# MSSRP-Microcontroller.net
KiCad netlist of a schematic drawn in EAGLE
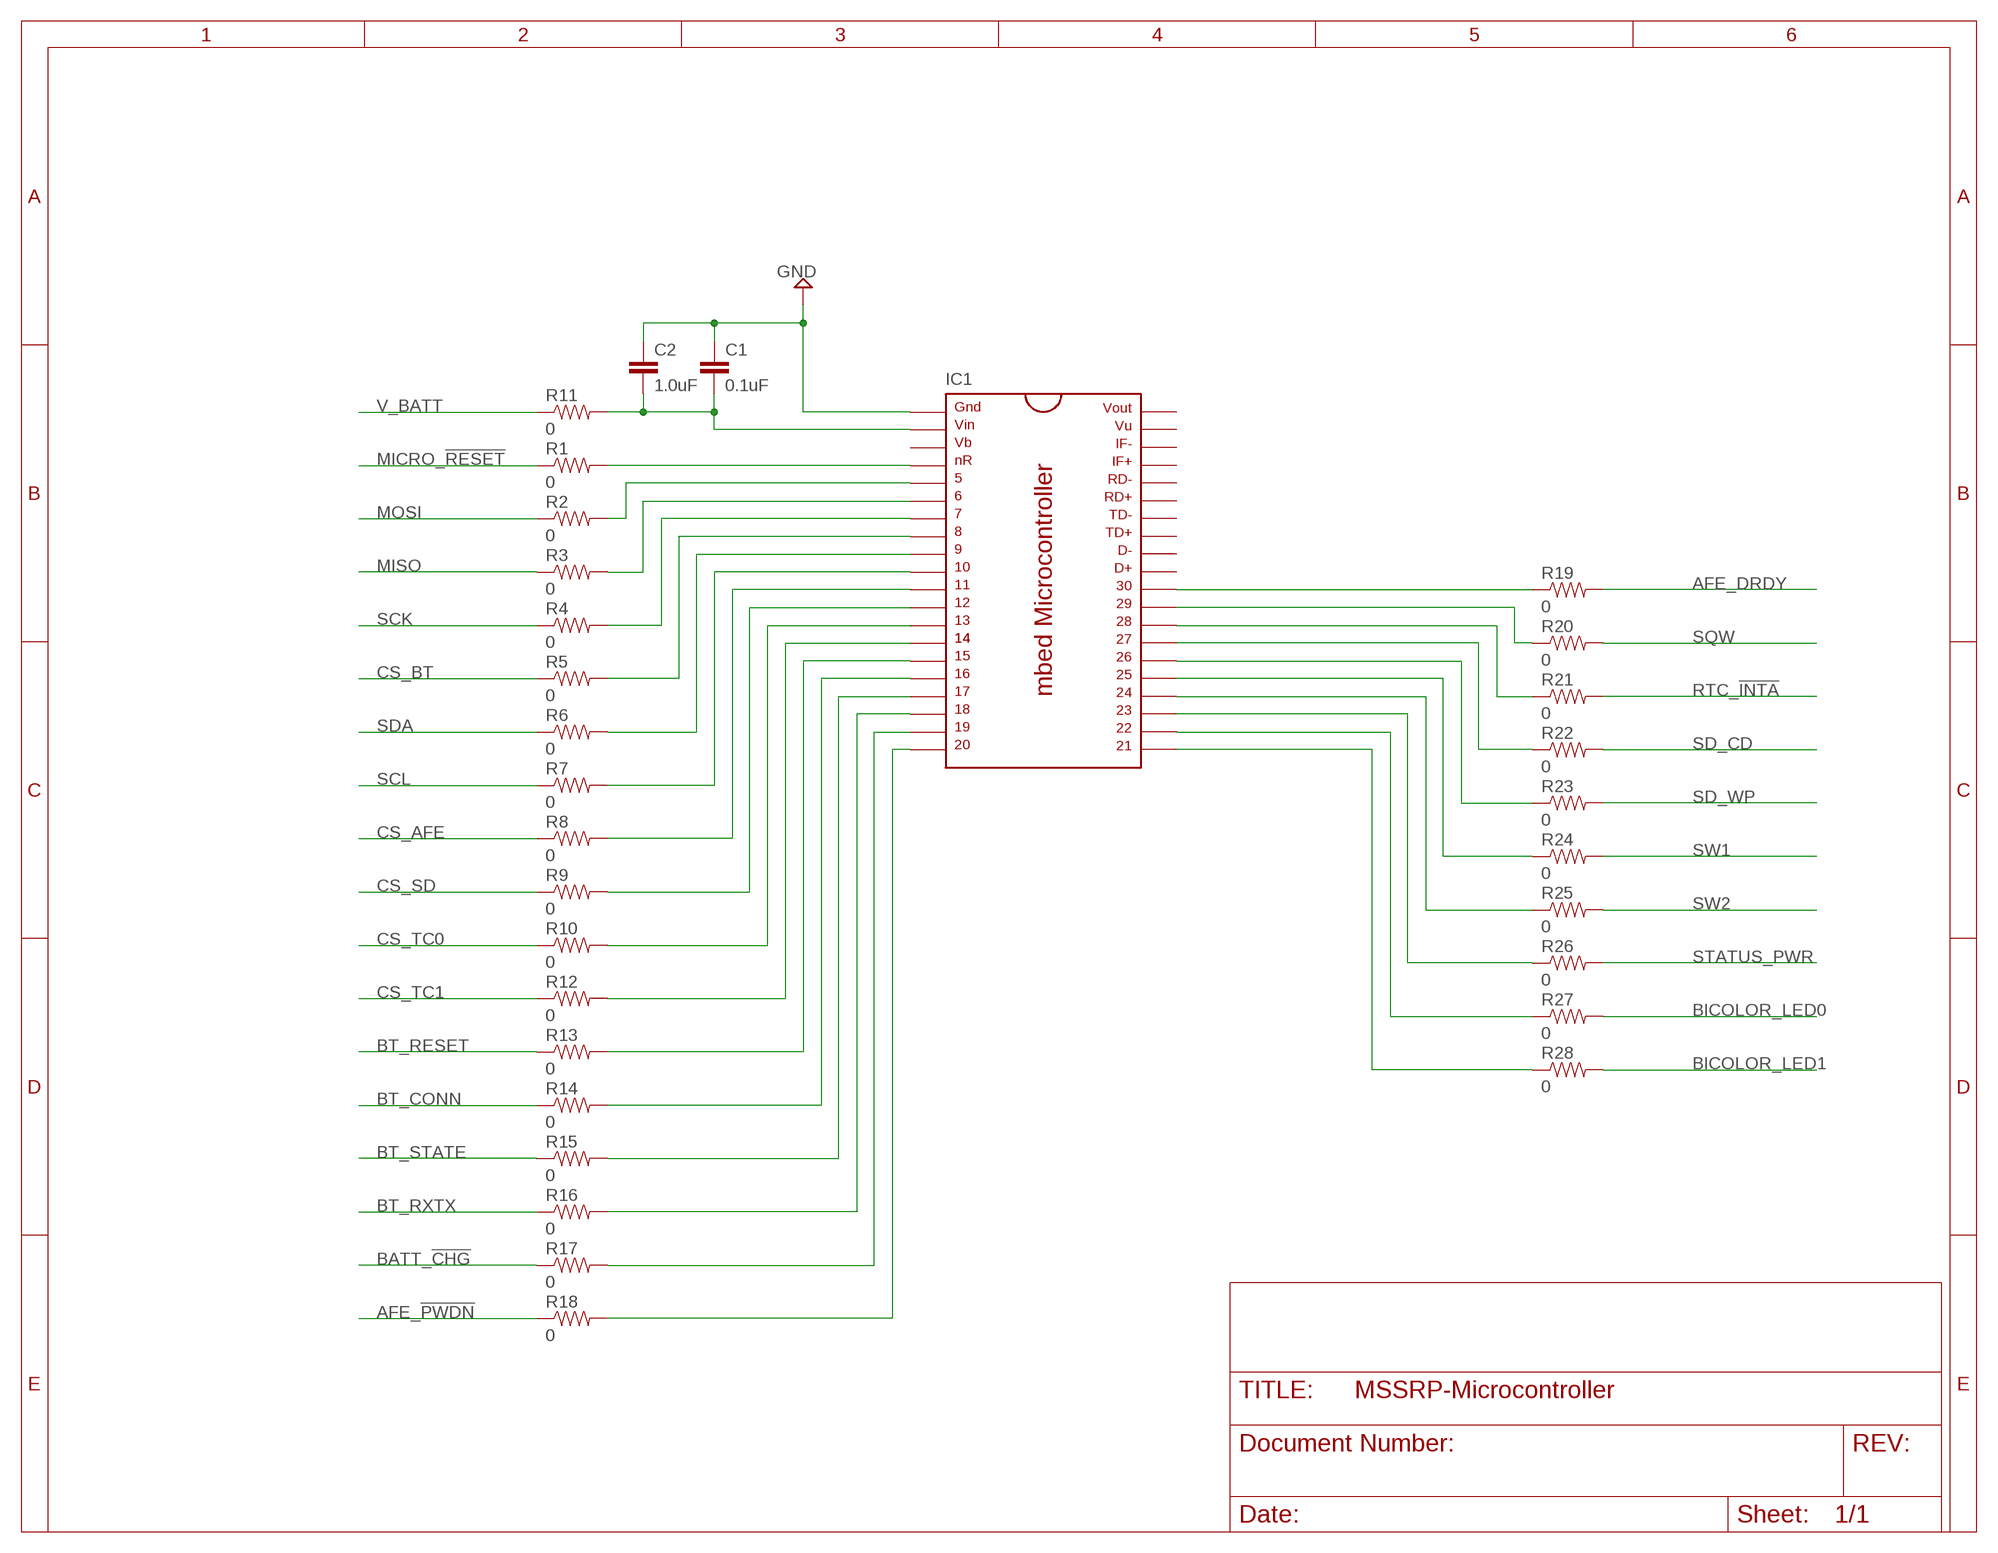
[diagram p0: schematic, sheet 1]

(export (version "E")
  (design (tool "Eeschema 10.0.6"))
  (components
    (comp (ref "C1")
      (value "0.1uF")
      (footprint "eagle-import:0603-CAP")
      (libsource (lib "eagle-import") (part "0.1UF-25V-5%(0603)"))
    )
    (comp (ref "C2")
      (value "1.0uF")
      (footprint "eagle-import:0603-CAP")
      (libsource (lib "eagle-import") (part "1.0UF-16V-10%(0603)"))
    )
    (comp (ref "IC1")
      (value "MBED")
      (footprint "eagle-import:DIL40_0.9")
      (libsource (lib "eagle-import") (part "MBED"))
    )
    (comp (ref "R1")
      (value "0")
      (footprint "eagle-import:0603")
      (libsource (lib "eagle-import") (part "0OHM1/10W5%(0603)"))
    )
    (comp (ref "R2")
      (value "0")
      (footprint "eagle-import:0603")
      (libsource (lib "eagle-import") (part "0OHM1/10W5%(0603)"))
    )
    (comp (ref "R3")
      (value "0")
      (footprint "eagle-import:0603")
      (libsource (lib "eagle-import") (part "0OHM1/10W5%(0603)"))
    )
    (comp (ref "R4")
      (value "0")
      (footprint "eagle-import:0603")
      (libsource (lib "eagle-import") (part "0OHM1/10W5%(0603)"))
    )
    (comp (ref "R5")
      (value "0")
      (footprint "eagle-import:0603")
      (libsource (lib "eagle-import") (part "0OHM1/10W5%(0603)"))
    )
    (comp (ref "R6")
      (value "0")
      (footprint "eagle-import:0603")
      (libsource (lib "eagle-import") (part "0OHM1/10W5%(0603)"))
    )
    (comp (ref "R7")
      (value "0")
      (footprint "eagle-import:0603")
      (libsource (lib "eagle-import") (part "0OHM1/10W5%(0603)"))
    )
    (comp (ref "R8")
      (value "0")
      (footprint "eagle-import:0603")
      (libsource (lib "eagle-import") (part "0OHM1/10W5%(0603)"))
    )
    (comp (ref "R9")
      (value "0")
      (footprint "eagle-import:0603")
      (libsource (lib "eagle-import") (part "0OHM1/10W5%(0603)"))
    )
    (comp (ref "R10")
      (value "0")
      (footprint "eagle-import:0603")
      (libsource (lib "eagle-import") (part "0OHM1/10W5%(0603)"))
    )
    (comp (ref "R11")
      (value "0")
      (footprint "eagle-import:0603")
      (libsource (lib "eagle-import") (part "0OHM1/10W5%(0603)"))
    )
    (comp (ref "R12")
      (value "0")
      (footprint "eagle-import:0603")
      (libsource (lib "eagle-import") (part "0OHM1/10W5%(0603)"))
    )
    (comp (ref "R13")
      (value "0")
      (footprint "eagle-import:0603")
      (libsource (lib "eagle-import") (part "0OHM1/10W5%(0603)"))
    )
    (comp (ref "R14")
      (value "0")
      (footprint "eagle-import:0603")
      (libsource (lib "eagle-import") (part "0OHM1/10W5%(0603)"))
    )
    (comp (ref "R15")
      (value "0")
      (footprint "eagle-import:0603")
      (libsource (lib "eagle-import") (part "0OHM1/10W5%(0603)"))
    )
    (comp (ref "R16")
      (value "0")
      (footprint "eagle-import:0603")
      (libsource (lib "eagle-import") (part "0OHM1/10W5%(0603)"))
    )
    (comp (ref "R17")
      (value "0")
      (footprint "eagle-import:0603")
      (libsource (lib "eagle-import") (part "0OHM1/10W5%(0603)"))
    )
    (comp (ref "R18")
      (value "0")
      (footprint "eagle-import:0603")
      (libsource (lib "eagle-import") (part "0OHM1/10W5%(0603)"))
    )
    (comp (ref "R19")
      (value "0")
      (footprint "eagle-import:0603")
      (libsource (lib "eagle-import") (part "0OHM1/10W5%(0603)"))
    )
    (comp (ref "R20")
      (value "0")
      (footprint "eagle-import:0603")
      (libsource (lib "eagle-import") (part "0OHM1/10W5%(0603)"))
    )
    (comp (ref "R21")
      (value "0")
      (footprint "eagle-import:0603")
      (libsource (lib "eagle-import") (part "0OHM1/10W5%(0603)"))
    )
    (comp (ref "R22")
      (value "0")
      (footprint "eagle-import:0603")
      (libsource (lib "eagle-import") (part "0OHM1/10W5%(0603)"))
    )
    (comp (ref "R23")
      (value "0")
      (footprint "eagle-import:0603")
      (libsource (lib "eagle-import") (part "0OHM1/10W5%(0603)"))
    )
    (comp (ref "R24")
      (value "0")
      (footprint "eagle-import:0603")
      (libsource (lib "eagle-import") (part "0OHM1/10W5%(0603)"))
    )
    (comp (ref "R25")
      (value "0")
      (footprint "eagle-import:0603")
      (libsource (lib "eagle-import") (part "0OHM1/10W5%(0603)"))
    )
    (comp (ref "R26")
      (value "0")
      (footprint "eagle-import:0603")
      (libsource (lib "eagle-import") (part "0OHM1/10W5%(0603)"))
    )
    (comp (ref "R27")
      (value "0")
      (footprint "eagle-import:0603")
      (libsource (lib "eagle-import") (part "0OHM1/10W5%(0603)"))
    )
    (comp (ref "R28")
      (value "0")
      (footprint "eagle-import:0603")
      (libsource (lib "eagle-import") (part "0OHM1/10W5%(0603)"))
    )
  )
  (nets
    (net (code "1") (name "/AFE_DRDY") (class "Default")
      (node (ref "R19") (pin "2") (pinfunction "2_2") (pintype "passive"))
    )
    (net (code "2") (name "/AFE_~{PWDN}") (class "Default")
      (node (ref "R18") (pin "1") (pinfunction "1_1") (pintype "passive"))
    )
    (net (code "3") (name "/BATT_~{CHG}") (class "Default")
      (node (ref "R17") (pin "1") (pinfunction "1_1") (pintype "passive"))
    )
    (net (code "4") (name "/BICOLOR_LED0") (class "Default")
      (node (ref "R27") (pin "2") (pinfunction "2_2") (pintype "passive"))
    )
    (net (code "5") (name "/BICOLOR_LED1") (class "Default")
      (node (ref "R28") (pin "2") (pinfunction "2_2") (pintype "passive"))
    )
    (net (code "6") (name "/BT_CONN") (class "Default")
      (node (ref "R14") (pin "1") (pinfunction "1_1") (pintype "passive"))
    )
    (net (code "7") (name "/BT_RESET") (class "Default")
      (node (ref "R13") (pin "1") (pinfunction "1_1") (pintype "passive"))
    )
    (net (code "8") (name "/BT_RXTX") (class "Default")
      (node (ref "R16") (pin "1") (pinfunction "1_1") (pintype "passive"))
    )
    (net (code "9") (name "/BT_STATE") (class "Default")
      (node (ref "R15") (pin "1") (pinfunction "1_1") (pintype "passive"))
    )
    (net (code "10") (name "/CS_AFE") (class "Default")
      (node (ref "R8") (pin "1") (pinfunction "1_1") (pintype "passive"))
    )
    (net (code "11") (name "/CS_BT") (class "Default")
      (node (ref "R5") (pin "1") (pinfunction "1_1") (pintype "passive"))
    )
    (net (code "12") (name "/CS_SD") (class "Default")
      (node (ref "R9") (pin "1") (pinfunction "1_1") (pintype "passive"))
    )
    (net (code "13") (name "/CS_TC0") (class "Default")
      (node (ref "R10") (pin "1") (pinfunction "1_1") (pintype "passive"))
    )
    (net (code "14") (name "/CS_TC1") (class "Default")
      (node (ref "R12") (pin "1") (pinfunction "1_1") (pintype "passive"))
    )
    (net (code "15") (name "/MICRO_~{RESET}") (class "Default")
      (node (ref "R1") (pin "1") (pinfunction "1_1") (pintype "passive"))
    )
    (net (code "16") (name "/MISO") (class "Default")
      (node (ref "R3") (pin "1") (pinfunction "1_1") (pintype "passive"))
    )
    (net (code "17") (name "/MOSI") (class "Default")
      (node (ref "R2") (pin "1") (pinfunction "1_1") (pintype "passive"))
    )
    (net (code "18") (name "/RTC_~{INTA}") (class "Default")
      (node (ref "R21") (pin "2") (pinfunction "2_2") (pintype "passive"))
    )
    (net (code "19") (name "/SCK") (class "Default")
      (node (ref "R4") (pin "1") (pinfunction "1_1") (pintype "passive"))
    )
    (net (code "20") (name "/SCL") (class "Default")
      (node (ref "R7") (pin "1") (pinfunction "1_1") (pintype "passive"))
    )
    (net (code "21") (name "/SDA") (class "Default")
      (node (ref "R6") (pin "1") (pinfunction "1_1") (pintype "passive"))
    )
    (net (code "22") (name "/SD_CD") (class "Default")
      (node (ref "R22") (pin "2") (pinfunction "2_2") (pintype "passive"))
    )
    (net (code "23") (name "/SD_WP") (class "Default")
      (node (ref "R23") (pin "2") (pinfunction "2_2") (pintype "passive"))
    )
    (net (code "24") (name "/SQW") (class "Default")
      (node (ref "R20") (pin "2") (pinfunction "2_2") (pintype "passive"))
    )
    (net (code "25") (name "/STATUS_PWR") (class "Default")
      (node (ref "R26") (pin "2") (pinfunction "2_2") (pintype "passive"))
    )
    (net (code "26") (name "/SW1") (class "Default")
      (node (ref "R24") (pin "2") (pinfunction "2_2") (pintype "passive"))
    )
    (net (code "27") (name "/SW2") (class "Default")
      (node (ref "R25") (pin "2") (pinfunction "2_2") (pintype "passive"))
    )
    (net (code "28") (name "/V_BATT") (class "Default")
      (node (ref "R11") (pin "1") (pinfunction "1_1") (pintype "passive"))
    )
    (net (code "29") (name "GND") (class "Default")
      (node (ref "C1") (pin "1") (pinfunction "1_1") (pintype "passive"))
      (node (ref "C2") (pin "1") (pinfunction "1_1") (pintype "passive"))
      (node (ref "IC1") (pin "1") (pinfunction "P$1_1") (pintype "bidirectional"))
    )
    (net (code "30") (name "Net-(IC1-P$2)") (class "Default")
      (node (ref "C1") (pin "2") (pinfunction "2_2") (pintype "passive"))
      (node (ref "C2") (pin "2") (pinfunction "2_2") (pintype "passive"))
      (node (ref "IC1") (pin "2") (pinfunction "P$2_2") (pintype "bidirectional"))
      (node (ref "R11") (pin "2") (pinfunction "2_2") (pintype "passive"))
    )
    (net (code "31") (name "Net-(IC1-P$4)") (class "Default")
      (node (ref "IC1") (pin "4") (pinfunction "P$4_4") (pintype "bidirectional"))
      (node (ref "R1") (pin "2") (pinfunction "2_2") (pintype "passive"))
    )
    (net (code "32") (name "Net-(IC1-P$5)") (class "Default")
      (node (ref "IC1") (pin "5") (pinfunction "P$5_5") (pintype "bidirectional"))
      (node (ref "R2") (pin "2") (pinfunction "2_2") (pintype "passive"))
    )
    (net (code "33") (name "Net-(IC1-P$6)") (class "Default")
      (node (ref "IC1") (pin "6") (pinfunction "P$6_6") (pintype "bidirectional"))
      (node (ref "R3") (pin "2") (pinfunction "2_2") (pintype "passive"))
    )
    (net (code "34") (name "Net-(IC1-P$7)") (class "Default")
      (node (ref "IC1") (pin "7") (pinfunction "P$7_7") (pintype "bidirectional"))
      (node (ref "R4") (pin "2") (pinfunction "2_2") (pintype "passive"))
    )
    (net (code "35") (name "Net-(IC1-P$8)") (class "Default")
      (node (ref "IC1") (pin "8") (pinfunction "P$8_8") (pintype "bidirectional"))
      (node (ref "R5") (pin "2") (pinfunction "2_2") (pintype "passive"))
    )
    (net (code "36") (name "Net-(IC1-P$9)") (class "Default")
      (node (ref "IC1") (pin "9") (pinfunction "P$9_9") (pintype "bidirectional"))
      (node (ref "R6") (pin "2") (pinfunction "2_2") (pintype "passive"))
    )
    (net (code "37") (name "Net-(IC1-P$10)") (class "Default")
      (node (ref "IC1") (pin "10") (pinfunction "P$10_10") (pintype "bidirectional"))
      (node (ref "R7") (pin "2") (pinfunction "2_2") (pintype "passive"))
    )
    (net (code "38") (name "Net-(IC1-P$11)") (class "Default")
      (node (ref "IC1") (pin "11") (pinfunction "P$11_11") (pintype "bidirectional"))
      (node (ref "R8") (pin "2") (pinfunction "2_2") (pintype "passive"))
    )
    (net (code "39") (name "Net-(IC1-P$12)") (class "Default")
      (node (ref "IC1") (pin "12") (pinfunction "P$12_12") (pintype "bidirectional"))
      (node (ref "R9") (pin "2") (pinfunction "2_2") (pintype "passive"))
    )
    (net (code "40") (name "Net-(IC1-P$13)") (class "Default")
      (node (ref "IC1") (pin "13") (pinfunction "P$13_13") (pintype "bidirectional"))
      (node (ref "R10") (pin "2") (pinfunction "2_2") (pintype "passive"))
    )
    (net (code "41") (name "Net-(IC1-P$14)") (class "Default")
      (node (ref "IC1") (pin "14") (pinfunction "P$14_14") (pintype "bidirectional"))
      (node (ref "R12") (pin "2") (pinfunction "2_2") (pintype "passive"))
    )
    (net (code "42") (name "Net-(IC1-P$15)") (class "Default")
      (node (ref "IC1") (pin "15") (pinfunction "P$15_15") (pintype "bidirectional"))
      (node (ref "R13") (pin "2") (pinfunction "2_2") (pintype "passive"))
    )
    (net (code "43") (name "Net-(IC1-P$16)") (class "Default")
      (node (ref "IC1") (pin "16") (pinfunction "P$16_16") (pintype "bidirectional"))
      (node (ref "R14") (pin "2") (pinfunction "2_2") (pintype "passive"))
    )
    (net (code "44") (name "Net-(IC1-P$17)") (class "Default")
      (node (ref "IC1") (pin "17") (pinfunction "P$17_17") (pintype "bidirectional"))
      (node (ref "R15") (pin "2") (pinfunction "2_2") (pintype "passive"))
    )
    (net (code "45") (name "Net-(IC1-P$18)") (class "Default")
      (node (ref "IC1") (pin "18") (pinfunction "P$18_18") (pintype "bidirectional"))
      (node (ref "R16") (pin "2") (pinfunction "2_2") (pintype "passive"))
    )
    (net (code "46") (name "Net-(IC1-P$19)") (class "Default")
      (node (ref "IC1") (pin "19") (pinfunction "P$19_19") (pintype "bidirectional"))
      (node (ref "R17") (pin "2") (pinfunction "2_2") (pintype "passive"))
    )
    (net (code "47") (name "Net-(IC1-P$20)") (class "Default")
      (node (ref "IC1") (pin "20") (pinfunction "P$20_20") (pintype "bidirectional"))
      (node (ref "R18") (pin "2") (pinfunction "2_2") (pintype "passive"))
    )
    (net (code "48") (name "Net-(IC1-P$21)") (class "Default")
      (node (ref "IC1") (pin "21") (pinfunction "P$21_21") (pintype "bidirectional"))
      (node (ref "R28") (pin "1") (pinfunction "1_1") (pintype "passive"))
    )
    (net (code "49") (name "Net-(IC1-P$22)") (class "Default")
      (node (ref "IC1") (pin "22") (pinfunction "P$22_22") (pintype "bidirectional"))
      (node (ref "R27") (pin "1") (pinfunction "1_1") (pintype "passive"))
    )
    (net (code "50") (name "Net-(IC1-P$23)") (class "Default")
      (node (ref "IC1") (pin "23") (pinfunction "P$23_23") (pintype "bidirectional"))
      (node (ref "R26") (pin "1") (pinfunction "1_1") (pintype "passive"))
    )
    (net (code "51") (name "Net-(IC1-P$24)") (class "Default")
      (node (ref "IC1") (pin "24") (pinfunction "P$24_24") (pintype "bidirectional"))
      (node (ref "R25") (pin "1") (pinfunction "1_1") (pintype "passive"))
    )
    (net (code "52") (name "Net-(IC1-P$25)") (class "Default")
      (node (ref "IC1") (pin "25") (pinfunction "P$25_25") (pintype "bidirectional"))
      (node (ref "R24") (pin "1") (pinfunction "1_1") (pintype "passive"))
    )
    (net (code "53") (name "Net-(IC1-P$26)") (class "Default")
      (node (ref "IC1") (pin "26") (pinfunction "P$26_26") (pintype "bidirectional"))
      (node (ref "R23") (pin "1") (pinfunction "1_1") (pintype "passive"))
    )
    (net (code "54") (name "Net-(IC1-P$27)") (class "Default")
      (node (ref "IC1") (pin "27") (pinfunction "P$27_27") (pintype "bidirectional"))
      (node (ref "R22") (pin "1") (pinfunction "1_1") (pintype "passive"))
    )
    (net (code "55") (name "Net-(IC1-P$28)") (class "Default")
      (node (ref "IC1") (pin "28") (pinfunction "P$28_28") (pintype "bidirectional"))
      (node (ref "R21") (pin "1") (pinfunction "1_1") (pintype "passive"))
    )
    (net (code "56") (name "Net-(IC1-P$29)") (class "Default")
      (node (ref "IC1") (pin "29") (pinfunction "P$29_29") (pintype "bidirectional"))
      (node (ref "R20") (pin "1") (pinfunction "1_1") (pintype "passive"))
    )
    (net (code "57") (name "Net-(IC1-P$30)") (class "Default")
      (node (ref "IC1") (pin "30") (pinfunction "P$30_30") (pintype "bidirectional"))
      (node (ref "R19") (pin "1") (pinfunction "1_1") (pintype "passive"))
    )
    (net (code "58") (name "unconnected-(IC1-P$3-Pad3)") (class "Default")
      (node (ref "IC1") (pin "3") (pinfunction "P$3_3") (pintype "bidirectional"))
    )
    (net (code "59") (name "unconnected-(IC1-P$31-Pad31)") (class "Default")
      (node (ref "IC1") (pin "31") (pinfunction "P$31_31") (pintype "bidirectional"))
    )
    (net (code "60") (name "unconnected-(IC1-P$32-Pad32)") (class "Default")
      (node (ref "IC1") (pin "32") (pinfunction "P$32_32") (pintype "bidirectional"))
    )
    (net (code "61") (name "unconnected-(IC1-P$33-Pad33)") (class "Default")
      (node (ref "IC1") (pin "33") (pinfunction "P$33_33") (pintype "bidirectional"))
    )
    (net (code "62") (name "unconnected-(IC1-P$34-Pad34)") (class "Default")
      (node (ref "IC1") (pin "34") (pinfunction "P$34_34") (pintype "bidirectional"))
    )
    (net (code "63") (name "unconnected-(IC1-P$35-Pad35)") (class "Default")
      (node (ref "IC1") (pin "35") (pinfunction "P$35_35") (pintype "bidirectional"))
    )
    (net (code "64") (name "unconnected-(IC1-P$36-Pad36)") (class "Default")
      (node (ref "IC1") (pin "36") (pinfunction "P$36_36") (pintype "bidirectional"))
    )
    (net (code "65") (name "unconnected-(IC1-P$37-Pad37)") (class "Default")
      (node (ref "IC1") (pin "37") (pinfunction "P$37_37") (pintype "bidirectional"))
    )
    (net (code "66") (name "unconnected-(IC1-P$38-Pad38)") (class "Default")
      (node (ref "IC1") (pin "38") (pinfunction "P$38_38") (pintype "bidirectional"))
    )
    (net (code "67") (name "unconnected-(IC1-P$39-Pad39)") (class "Default")
      (node (ref "IC1") (pin "39") (pinfunction "P$39_39") (pintype "bidirectional"))
    )
    (net (code "68") (name "unconnected-(IC1-P$40-Pad40)") (class "Default")
      (node (ref "IC1") (pin "40") (pinfunction "P$40_40") (pintype "bidirectional"))
    )
  )
)
